# Dimmer_Board_Rev_0_2.net
KiCad netlist of a schematic drawn in EAGLE
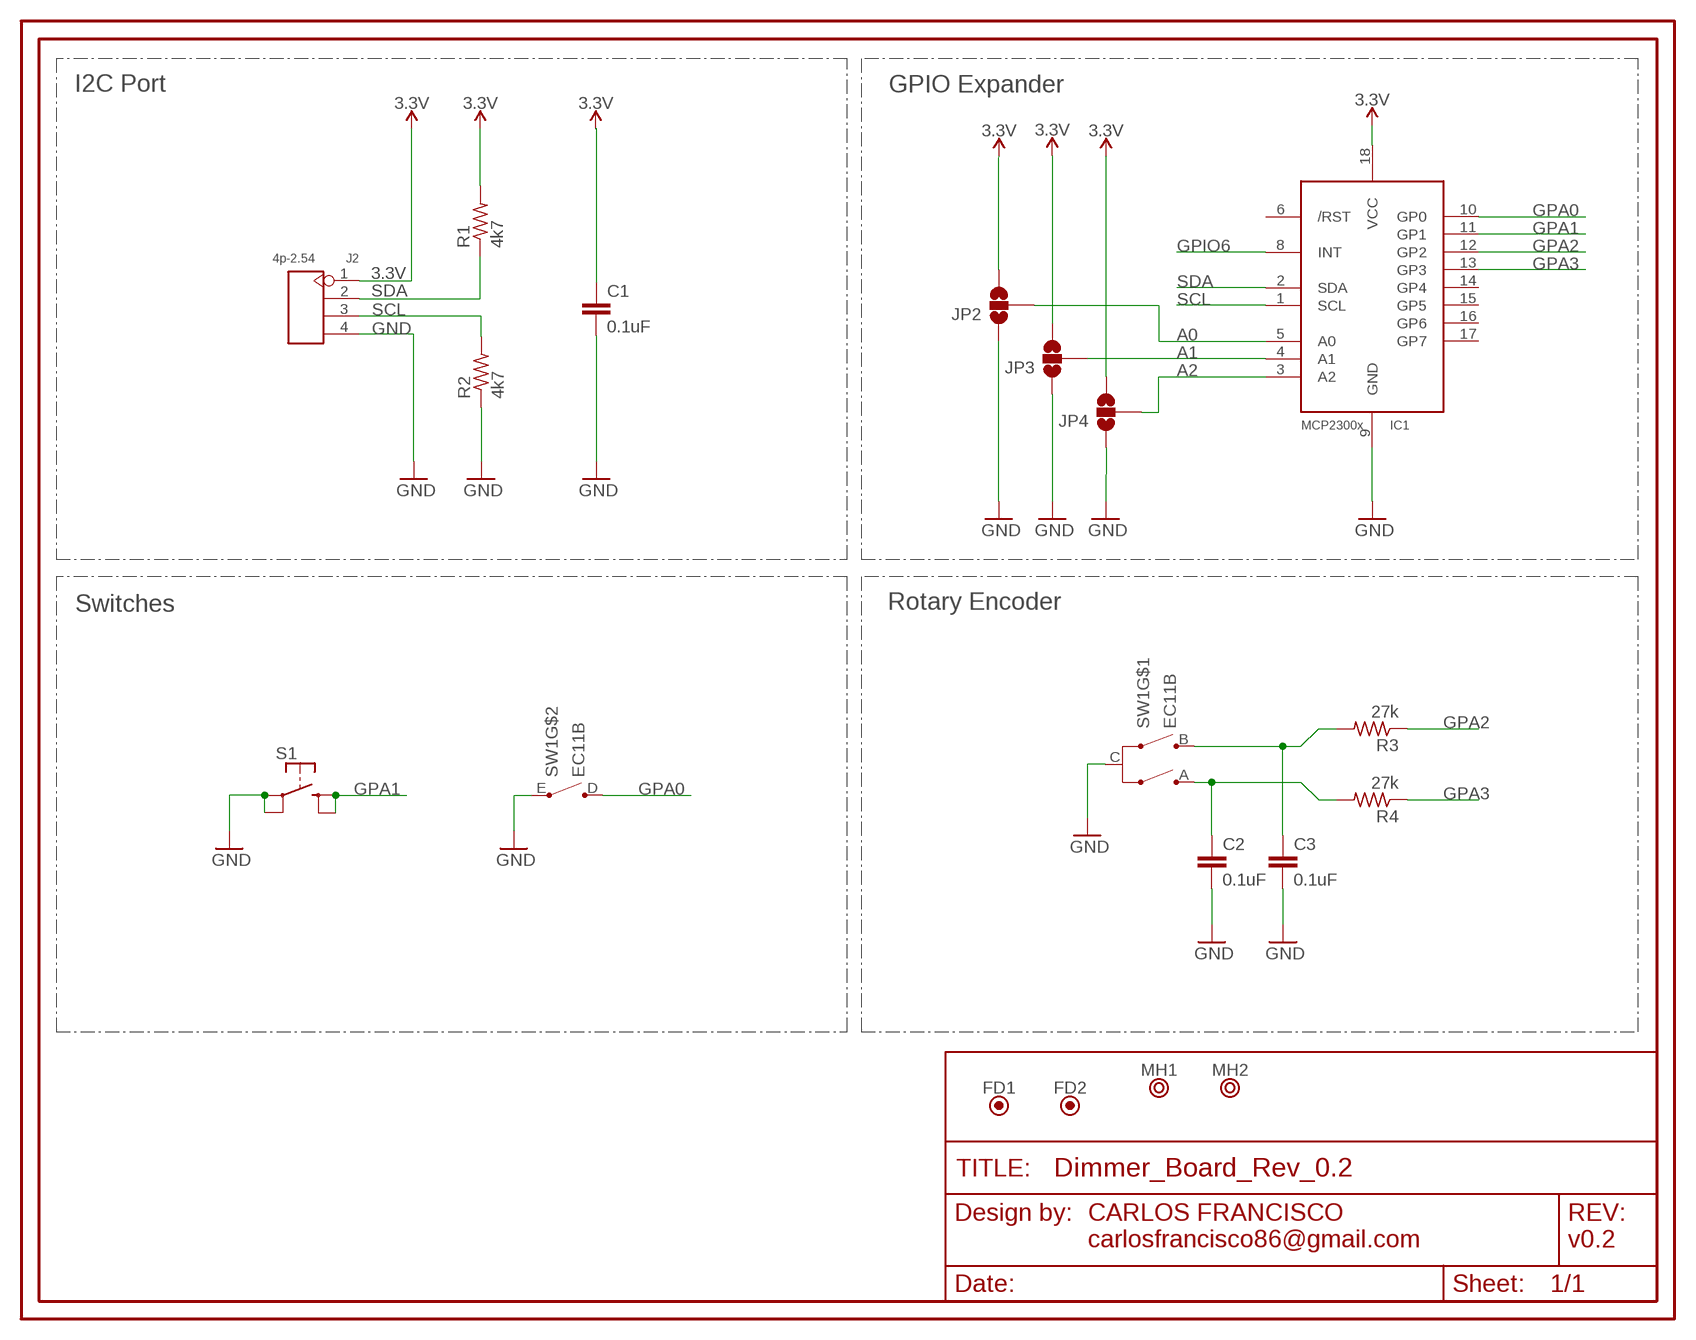
[diagram p0: schematic, sheet 1]

(export (version "E")
  (design (tool "Eeschema 10.0.6"))
  (components
    (comp (ref "C1")
      (value "0.1uF")
      (footprint "eagle-import:C0805")
      (libsource (lib "eagle-import") (part "C-EUC0805"))
    )
    (comp (ref "C2")
      (value "0.1uF")
      (footprint "eagle-import:C0805")
      (libsource (lib "eagle-import") (part "C-EUC0805"))
    )
    (comp (ref "C3")
      (value "0.1uF")
      (footprint "eagle-import:C0805")
      (libsource (lib "eagle-import") (part "C-EUC0805"))
    )
    (comp (ref "FD1")
      (value "FIDUCIALBFID")
      (footprint "eagle-import:BOARD_FIDUCIAL")
      (libsource (lib "eagle-import") (part "FIDUCIALBFID"))
    )
    (comp (ref "FD2")
      (value "FIDUCIALBFID")
      (footprint "eagle-import:BOARD_FIDUCIAL")
      (libsource (lib "eagle-import") (part "FIDUCIALBFID"))
    )
    (comp (ref "IC1")
      (value "MCP23008/SO")
      (footprint "eagle-import:SO18W")
      (libsource (lib "eagle-import") (part "MCP23008/SO"))
    )
    (comp (ref "J2")
      (value "4p-2.54")
      (footprint "eagle-import:H4-2.54")
      (fields (field (name "MPN") "P125-1104A0BS116A1"))
      (libsource (lib "eagle-import") (part "DIP-BLACK-MALE-HEADER-VERT(4P-2.54)"))
    )
    (comp (ref "JP2")
      (value "JUMPER-SMT_3_NO_SILK")
      (footprint "eagle-import:SMT-JUMPER_3_NO_SILK")
      (libsource (lib "eagle-import") (part "JUMPER-SMT_3_NO_SILK"))
    )
    (comp (ref "JP3")
      (value "JUMPER-SMT_3_NO_SILK")
      (footprint "eagle-import:SMT-JUMPER_3_NO_SILK")
      (libsource (lib "eagle-import") (part "JUMPER-SMT_3_NO_SILK"))
    )
    (comp (ref "JP4")
      (value "JUMPER-SMT_3_NO_SILK")
      (footprint "eagle-import:SMT-JUMPER_3_NO_SILK")
      (libsource (lib "eagle-import") (part "JUMPER-SMT_3_NO_SILK"))
    )
    (comp (ref "MH1")
      (value "MOUNTING_HOLE3.5MM")
      (footprint "eagle-import:MTGP500H350")
      (libsource (lib "eagle-import") (part "MOUNTING_HOLE3.5MM"))
    )
    (comp (ref "MH2")
      (value "MOUNTING_HOLE3.5MM")
      (footprint "eagle-import:MTGP500H350")
      (libsource (lib "eagle-import") (part "MOUNTING_HOLE3.5MM"))
    )
    (comp (ref "R1")
      (value "4k7")
      (footprint "eagle-import:R0805")
      (libsource (lib "eagle-import") (part "R-US_R0805"))
    )
    (comp (ref "R2")
      (value "4k7")
      (footprint "eagle-import:R0805")
      (libsource (lib "eagle-import") (part "R-US_R0805"))
    )
    (comp (ref "R3")
      (value "27k")
      (footprint "eagle-import:R0805")
      (libsource (lib "eagle-import") (part "R-US_R0805"))
    )
    (comp (ref "R4")
      (value "27k")
      (footprint "eagle-import:R0805")
      (libsource (lib "eagle-import") (part "R-US_R0805"))
    )
    (comp (ref "S1")
      (value "BUTTON-4KSC")
      (footprint "eagle-import:KSC_X")
      (libsource (lib "eagle-import") (part "BUTTON-4KSC"))
    )
    (comp (ref "SW1")
      (value "EC11B")
      (footprint "eagle-import:EC11B-V")
      (libsource (lib "eagle-import") (part "EC11B-V-T"))
    )
  )
  (nets
    (net (code "1") (name "/A0") (class "Default")
      (node (ref "IC1") (pin "5") (pinfunction "A0_5") (pintype "input"))
      (node (ref "JP2") (pin "2") (pinfunction "2_2") (pintype "passive"))
    )
    (net (code "2") (name "/A1") (class "Default")
      (node (ref "IC1") (pin "4") (pinfunction "A1_4") (pintype "input"))
      (node (ref "JP3") (pin "2") (pinfunction "2_2") (pintype "passive"))
    )
    (net (code "3") (name "/A2") (class "Default")
      (node (ref "IC1") (pin "3") (pinfunction "A2_3") (pintype "input"))
      (node (ref "JP4") (pin "2") (pinfunction "2_2") (pintype "passive"))
    )
    (net (code "4") (name "/GPA0") (class "Default")
      (node (ref "IC1") (pin "10") (pinfunction "GP0_10") (pintype "bidirectional"))
      (node (ref "SW1") (pin "D") (pinfunction "D_D") (pintype "passive"))
    )
    (net (code "5") (name "/GPA1") (class "Default")
      (node (ref "IC1") (pin "11") (pinfunction "GP1_11") (pintype "bidirectional"))
      (node (ref "S1") (pin "3") (pinfunction "3_3") (pintype "passive"))
      (node (ref "S1") (pin "4") (pinfunction "4_4") (pintype "passive"))
    )
    (net (code "6") (name "/GPA2") (class "Default")
      (node (ref "IC1") (pin "12") (pinfunction "GP2_12") (pintype "bidirectional"))
      (node (ref "R3") (pin "1") (pinfunction "1_1") (pintype "passive"))
    )
    (net (code "7") (name "/GPA3") (class "Default")
      (node (ref "IC1") (pin "13") (pinfunction "GP3_13") (pintype "bidirectional"))
      (node (ref "R4") (pin "1") (pinfunction "1_1") (pintype "passive"))
    )
    (net (code "8") (name "/GPIO6") (class "Default")
      (node (ref "IC1") (pin "8") (pinfunction "INT_8") (pintype "output"))
    )
    (net (code "9") (name "/SCL") (class "Default")
      (node (ref "IC1") (pin "1") (pinfunction "SCL_1") (pintype "bidirectional"))
      (node (ref "J2") (pin "3") (pinfunction "P$3_3") (pintype "bidirectional"))
      (node (ref "R2") (pin "2") (pinfunction "2_2") (pintype "passive"))
    )
    (net (code "10") (name "/SDA") (class "Default")
      (node (ref "IC1") (pin "2") (pinfunction "SDA_2") (pintype "bidirectional"))
      (node (ref "J2") (pin "2") (pinfunction "P$2_2") (pintype "bidirectional"))
      (node (ref "R1") (pin "1") (pinfunction "1_1") (pintype "passive"))
    )
    (net (code "11") (name "3.3V") (class "Default")
      (node (ref "C1") (pin "1") (pinfunction "1_1") (pintype "passive"))
      (node (ref "IC1") (pin "18") (pinfunction "VCC_18") (pintype "power_in"))
      (node (ref "J2") (pin "1") (pinfunction "P$1_1") (pintype "bidirectional"))
      (node (ref "JP2") (pin "3") (pinfunction "3_3") (pintype "passive"))
      (node (ref "JP3") (pin "3") (pinfunction "3_3") (pintype "passive"))
      (node (ref "JP4") (pin "3") (pinfunction "3_3") (pintype "passive"))
      (node (ref "R1") (pin "2") (pinfunction "2_2") (pintype "passive"))
    )
    (net (code "12") (name "GND") (class "Default")
      (node (ref "C1") (pin "2") (pinfunction "2_2") (pintype "passive"))
      (node (ref "C2") (pin "2") (pinfunction "2_2") (pintype "passive"))
      (node (ref "C3") (pin "2") (pinfunction "2_2") (pintype "passive"))
      (node (ref "IC1") (pin "9") (pinfunction "GND_9") (pintype "power_in"))
      (node (ref "J2") (pin "4") (pinfunction "P$4_4") (pintype "bidirectional"))
      (node (ref "JP2") (pin "1") (pinfunction "1_1") (pintype "passive"))
      (node (ref "JP3") (pin "1") (pinfunction "1_1") (pintype "passive"))
      (node (ref "JP4") (pin "1") (pinfunction "1_1") (pintype "passive"))
      (node (ref "R2") (pin "1") (pinfunction "1_1") (pintype "passive"))
      (node (ref "S1") (pin "1") (pinfunction "1_1") (pintype "passive"))
      (node (ref "S1") (pin "2") (pinfunction "2_2") (pintype "passive"))
      (node (ref "SW1") (pin "C") (pinfunction "C_C") (pintype "passive"))
      (node (ref "SW1") (pin "E") (pinfunction "E_E") (pintype "passive"))
    )
    (net (code "13") (name "Net-(C2-Pad1)") (class "Default")
      (node (ref "C2") (pin "1") (pinfunction "1_1") (pintype "passive"))
      (node (ref "R4") (pin "2") (pinfunction "2_2") (pintype "passive"))
      (node (ref "SW1") (pin "A") (pinfunction "A_A") (pintype "passive"))
    )
    (net (code "14") (name "Net-(C3-Pad1)") (class "Default")
      (node (ref "C3") (pin "1") (pinfunction "1_1") (pintype "passive"))
      (node (ref "R3") (pin "2") (pinfunction "2_2") (pintype "passive"))
      (node (ref "SW1") (pin "B") (pinfunction "B_B") (pintype "passive"))
    )
    (net (code "15") (name "unconnected-(IC1-GP4-Pad14)") (class "Default")
      (node (ref "IC1") (pin "14") (pinfunction "GP4_14") (pintype "bidirectional"))
    )
    (net (code "16") (name "unconnected-(IC1-GP5-Pad15)") (class "Default")
      (node (ref "IC1") (pin "15") (pinfunction "GP5_15") (pintype "bidirectional"))
    )
    (net (code "17") (name "unconnected-(IC1-GP6-Pad16)") (class "Default")
      (node (ref "IC1") (pin "16") (pinfunction "GP6_16") (pintype "bidirectional"))
    )
    (net (code "18") (name "unconnected-(IC1-GP7-Pad17)") (class "Default")
      (node (ref "IC1") (pin "17") (pinfunction "GP7_17") (pintype "bidirectional"))
    )
    (net (code "19") (name "unconnected-(IC1-{slash}RST-Pad6)") (class "Default")
      (node (ref "IC1") (pin "6") (pinfunction "/RST_6") (pintype "input"))
    )
    (net (code "20") (name "unconnected-(MH1-Pad1)") (class "Default")
      (node (ref "MH1") (pin "1") (pinfunction "1_1") (pintype "passive"))
    )
    (net (code "21") (name "unconnected-(MH2-Pad1)") (class "Default")
      (node (ref "MH2") (pin "1") (pinfunction "1_1") (pintype "passive"))
    )
  )
)
